# MotorDrive_REVA12.net
KiCad netlist of a schematic drawn in EAGLE
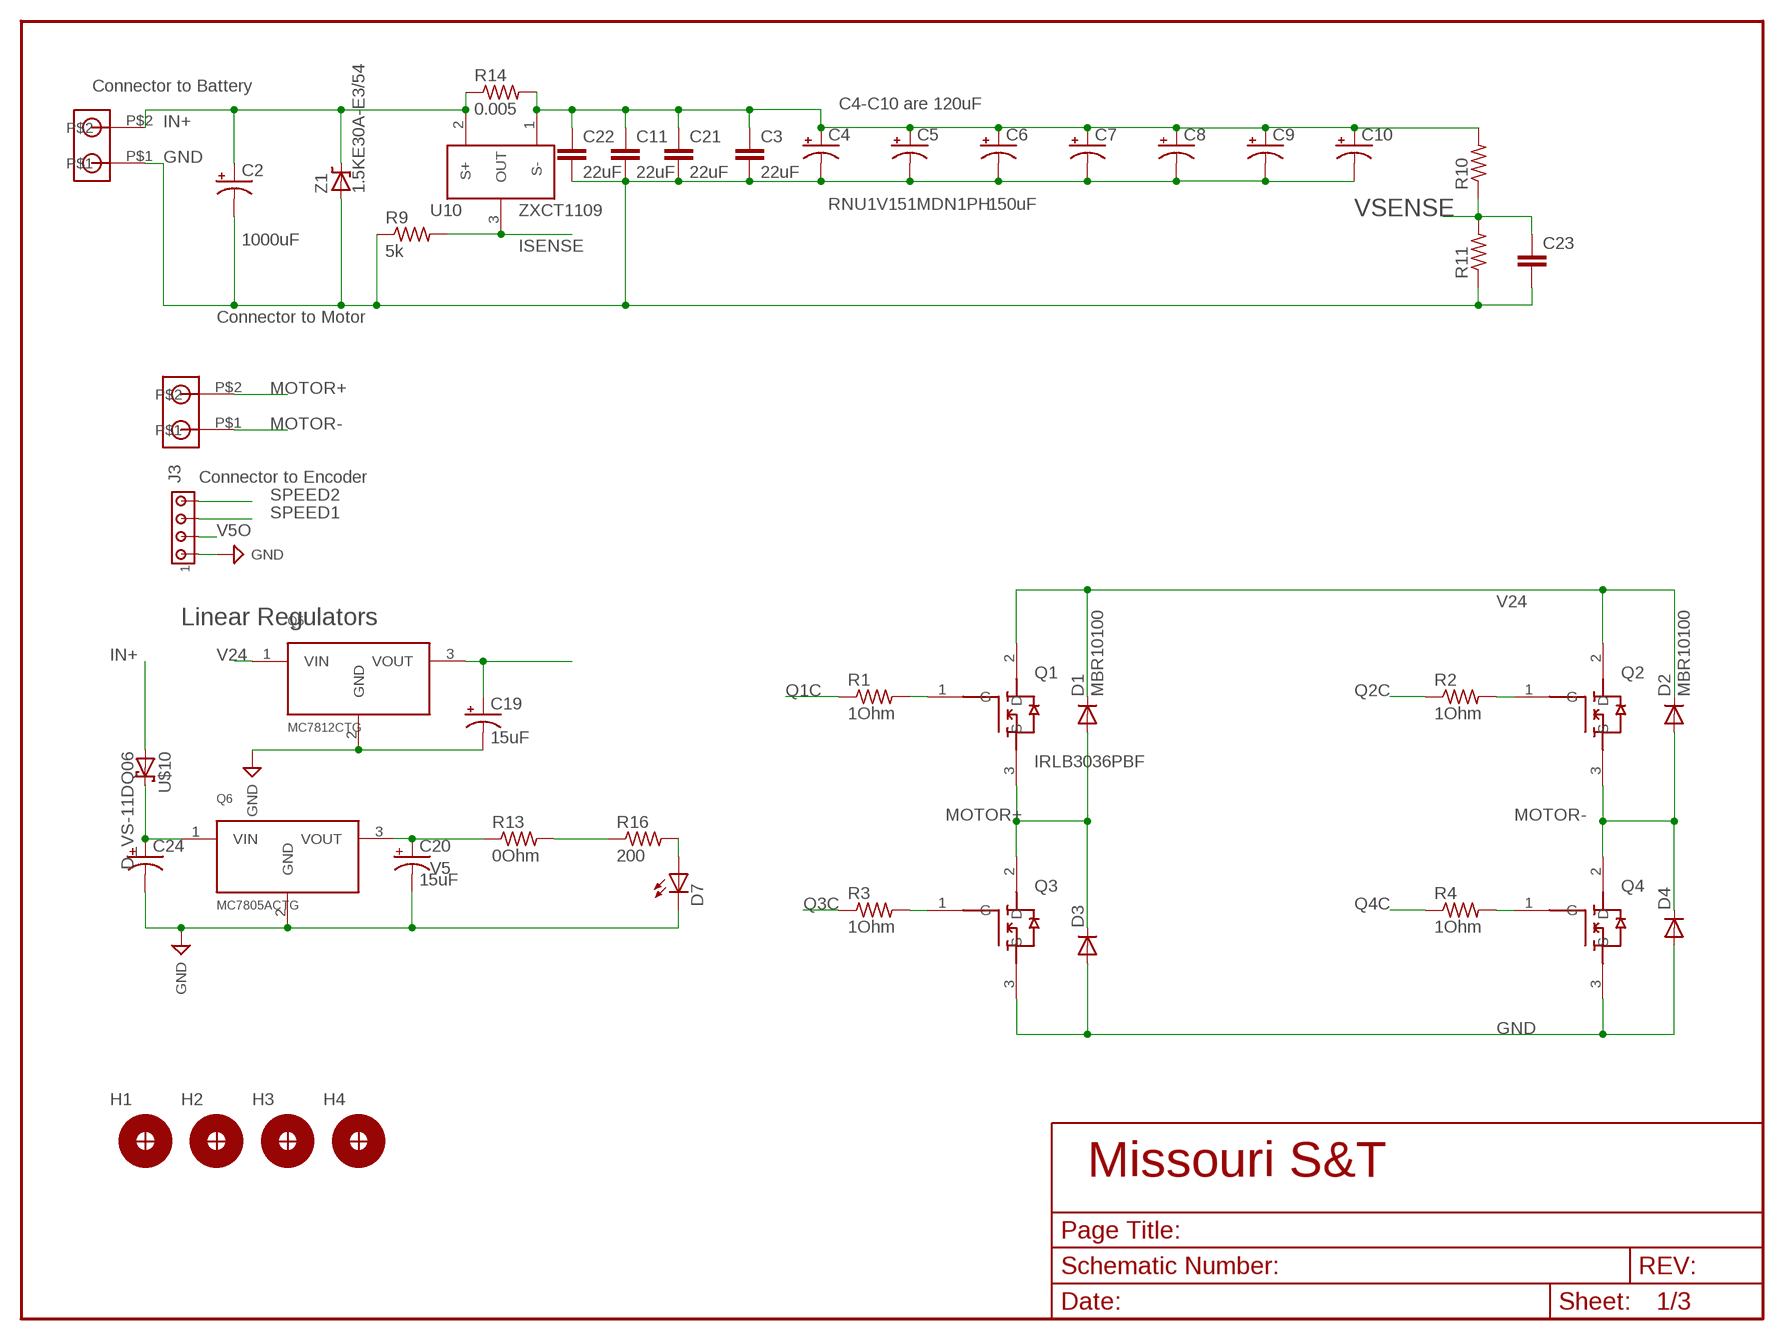
[diagram p0: schematic, sheet 1]
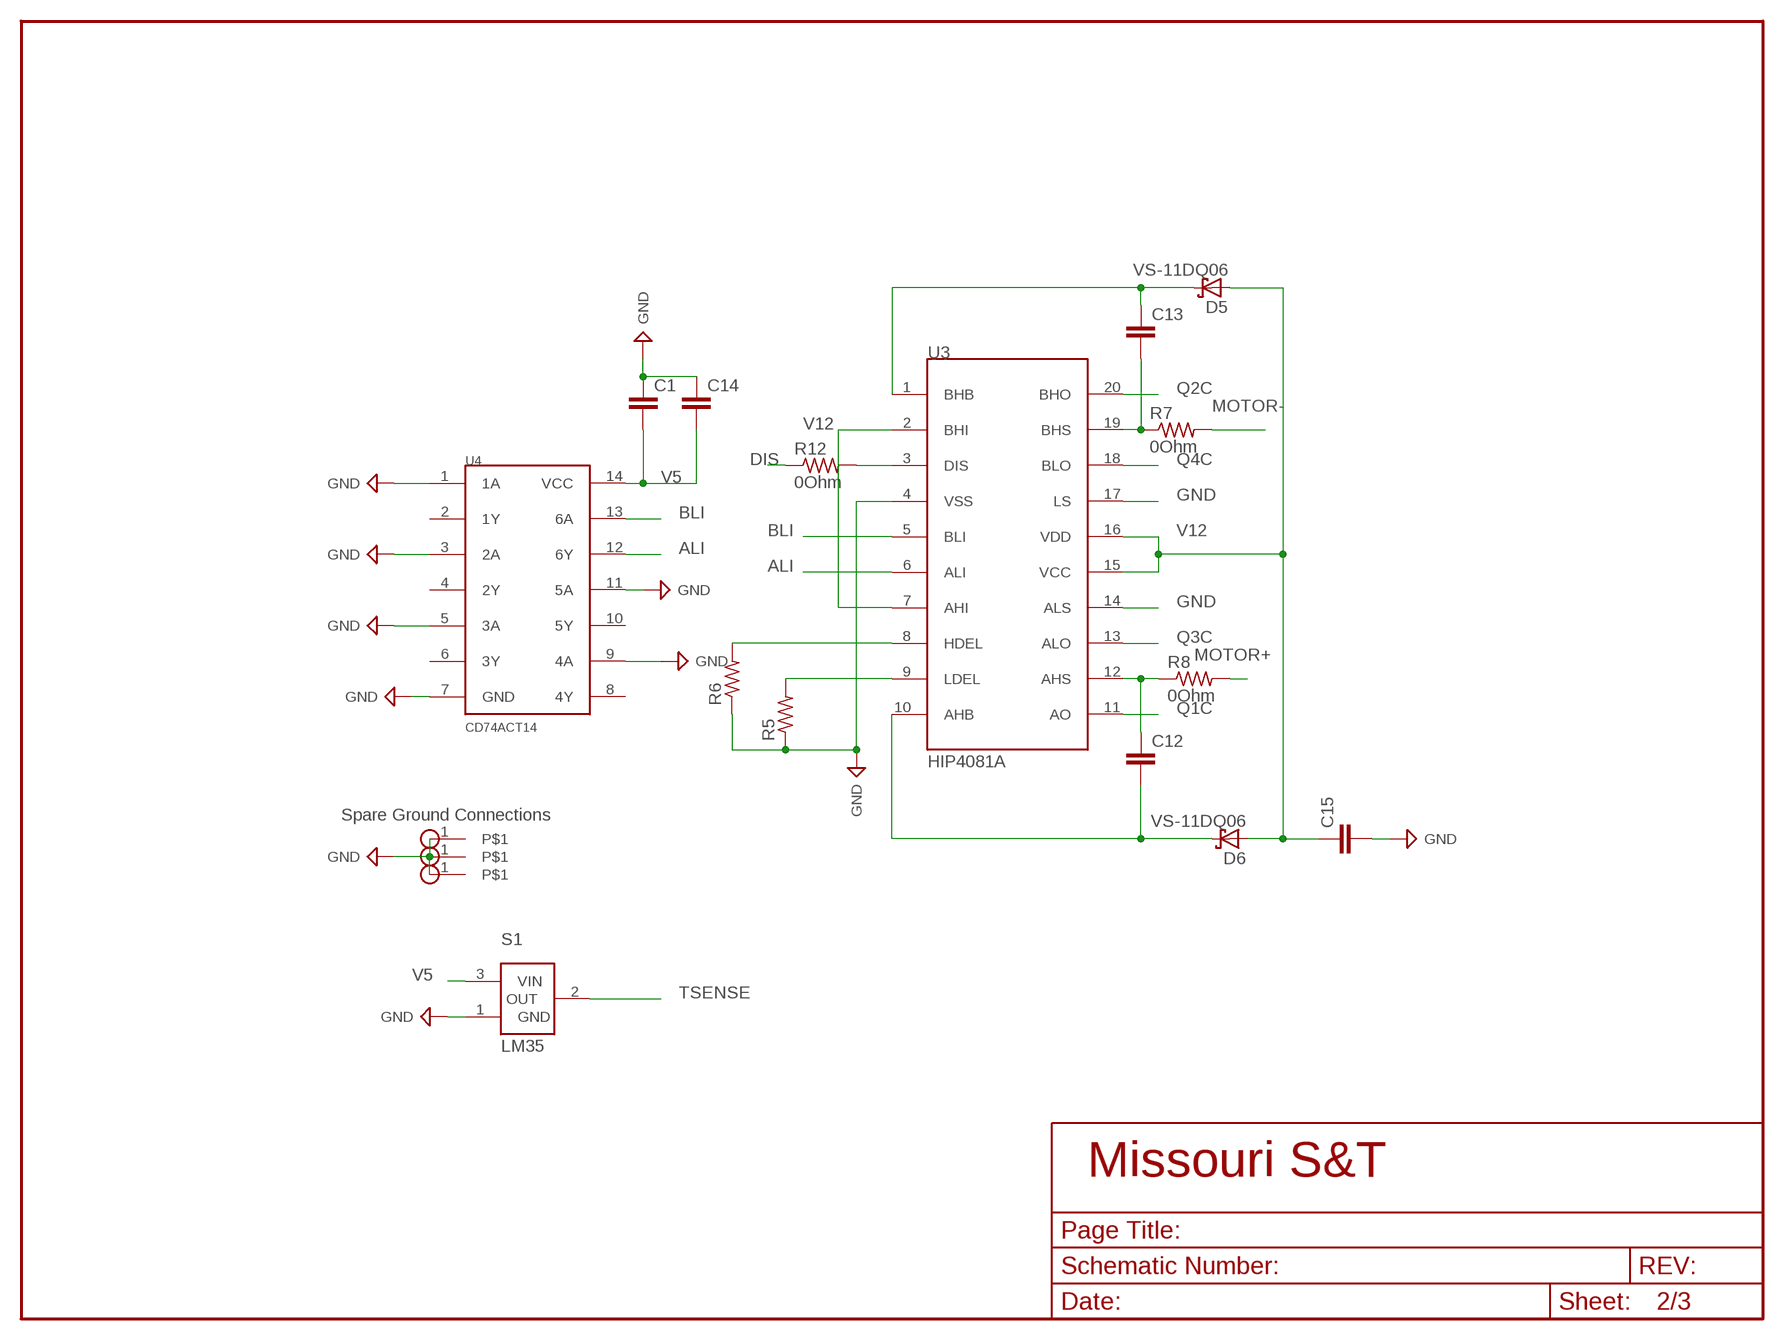
[diagram p1: schematic, sheet 2]
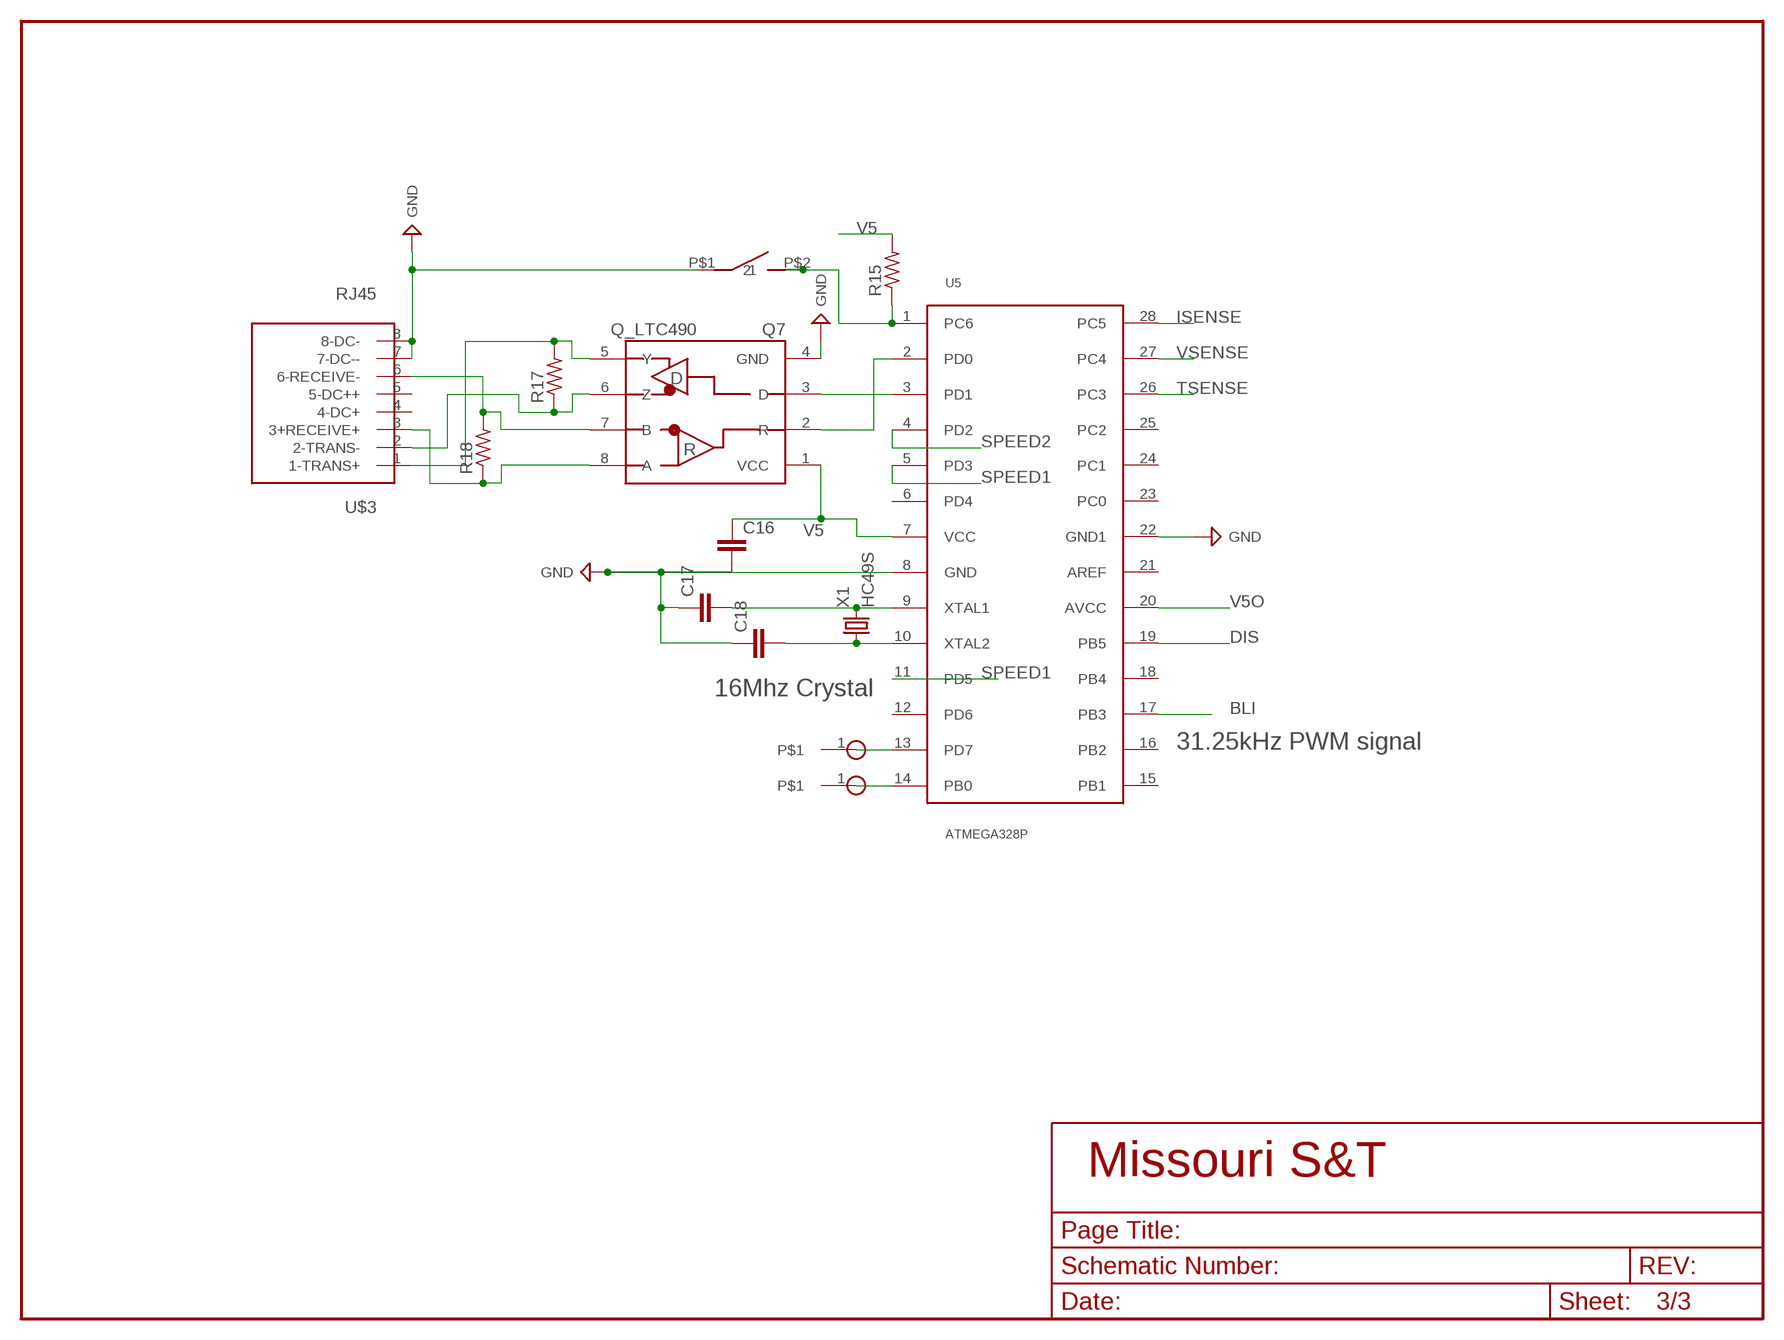
[diagram p2: schematic, sheet 3]

(export (version "E")
  (design (tool "Eeschema 10.0.6"))
  (components
    (comp (ref "C2")
      (value "1000uF")
      (footprint "eagle-import:C_10MM")
      (libsource (lib "eagle-import") (part "C_10MM"))
    )
    (comp (ref "C3")
      (value "22uF")
      (footprint "eagle-import:C_1206")
      (libsource (lib "eagle-import") (part "C_CAP_1206"))
    )
    (comp (ref "C4")
      (value "RNU1V151MDN1PH")
      (footprint "eagle-import:C_10MM")
      (libsource (lib "eagle-import") (part "C_10MM"))
    )
    (comp (ref "C5")
      (value "C_10MM")
      (footprint "eagle-import:C_10MM")
      (libsource (lib "eagle-import") (part "C_10MM"))
    )
    (comp (ref "C6")
      (value "C_10MM")
      (footprint "eagle-import:C_10MM")
      (libsource (lib "eagle-import") (part "C_10MM"))
    )
    (comp (ref "C7")
      (value "C_10MM")
      (footprint "eagle-import:C_10MM")
      (libsource (lib "eagle-import") (part "C_10MM"))
    )
    (comp (ref "C8")
      (value "C_10MM")
      (footprint "eagle-import:C_10MM")
      (libsource (lib "eagle-import") (part "C_10MM"))
    )
    (comp (ref "C9")
      (value "C_10MM")
      (footprint "eagle-import:C_10MM")
      (libsource (lib "eagle-import") (part "C_10MM"))
    )
    (comp (ref "C10")
      (value "150uF")
      (footprint "eagle-import:C_10MM")
      (libsource (lib "eagle-import") (part "C_10MM"))
    )
    (comp (ref "C11")
      (value "22uF")
      (footprint "eagle-import:C_1206")
      (libsource (lib "eagle-import") (part "C_CAP_1206"))
    )
    (comp (ref "C19")
      (value "15uF")
      (footprint "eagle-import:C_2MM")
      (libsource (lib "eagle-import") (part "C_GA1E150"))
    )
    (comp (ref "C20")
      (value "15uF")
      (footprint "eagle-import:C_2MM")
      (libsource (lib "eagle-import") (part "C_GA1E150"))
    )
    (comp (ref "C21")
      (value "22uF")
      (footprint "eagle-import:C_1206")
      (libsource (lib "eagle-import") (part "C_CAP_1206"))
    )
    (comp (ref "C22")
      (value "22uF")
      (footprint "eagle-import:C_1206")
      (libsource (lib "eagle-import") (part "C_CAP_1206"))
    )
    (comp (ref "C23")
      (value "C_CAP_1206")
      (footprint "eagle-import:C_1206")
      (libsource (lib "eagle-import") (part "C_CAP_1206"))
    )
    (comp (ref "C24")
      (value "C_POL_RAD_D8MM_LS200MIL_30MIL")
      (footprint "eagle-import:C_RAD_D8MM_LS200MIL_30MIL")
      (libsource (lib "eagle-import") (part "C_POL_RAD_D8MM_LS200MIL_30MIL"))
    )
    (comp (ref "D1")
      (value "MBR10100")
      (footprint "eagle-import:TO220AC")
      (libsource (lib "eagle-import") (part "D_FFPF10UA60ST"))
    )
    (comp (ref "D2")
      (value "MBR10100")
      (footprint "eagle-import:TO220AC")
      (libsource (lib "eagle-import") (part "D_FFPF10UA60ST"))
    )
    (comp (ref "D3")
      (value "D_FFPF10UA60ST")
      (footprint "eagle-import:TO220AC")
      (libsource (lib "eagle-import") (part "D_FFPF10UA60ST"))
    )
    (comp (ref "D4")
      (value "D_FFPF10UA60ST")
      (footprint "eagle-import:TO220AC")
      (libsource (lib "eagle-import") (part "D_FFPF10UA60ST"))
    )
    (comp (ref "D7")
      (value "D_LED_T1")
      (footprint "eagle-import:D_LED_T1")
      (libsource (lib "eagle-import") (part "D_LED_T1"))
    )
    (comp (ref "H1")
      (value "H_MNTHOLE_#4")
      (footprint "eagle-import:H_MNTHOLE_#4")
      (libsource (lib "eagle-import") (part "H_MNTHOLE_#4"))
    )
    (comp (ref "H2")
      (value "H_MNTHOLE_#4")
      (footprint "eagle-import:H_MNTHOLE_#4")
      (libsource (lib "eagle-import") (part "H_MNTHOLE_#4"))
    )
    (comp (ref "H3")
      (value "H_MNTHOLE_#4")
      (footprint "eagle-import:H_MNTHOLE_#4")
      (libsource (lib "eagle-import") (part "H_MNTHOLE_#4"))
    )
    (comp (ref "H4")
      (value "H_MNTHOLE_#4")
      (footprint "eagle-import:H_MNTHOLE_#4")
      (libsource (lib "eagle-import") (part "H_MNTHOLE_#4"))
    )
    (comp (ref "J1")
      (value "J_1546074-2")
      (footprint "eagle-import:THERM_BLOCK_2")
      (libsource (lib "eagle-import") (part "J_1546074-2"))
    )
    (comp (ref "J2")
      (value "J_1546074-2")
      (footprint "eagle-import:THERM_BLOCK_2")
      (libsource (lib "eagle-import") (part "J_1546074-2"))
    )
    (comp (ref "J3")
      (value "J_HDR1X4_MTA_100MIL")
      (footprint "eagle-import:J_MTA1X4_100MIL")
      (libsource (lib "eagle-import") (part "J_HDR1X4_MTA_100MIL"))
    )
    (comp (ref "Q1")
      (value "IRLB3036PBF")
      (footprint "eagle-import:TO220_6025DG")
      (libsource (lib "eagle-import") (part "Q_IRLB3036PBF"))
    )
    (comp (ref "Q2")
      (value "Q_IRLB3036PBF")
      (footprint "eagle-import:TO220_6025DG")
      (libsource (lib "eagle-import") (part "Q_IRLB3036PBF"))
    )
    (comp (ref "Q3")
      (value "Q_IRLB3036PBF")
      (footprint "eagle-import:TO220_6025DG")
      (libsource (lib "eagle-import") (part "Q_IRLB3036PBF"))
    )
    (comp (ref "Q4")
      (value "Q_IRLB3036PBF")
      (footprint "eagle-import:TO220_6025DG")
      (libsource (lib "eagle-import") (part "Q_IRLB3036PBF"))
    )
    (comp (ref "Q5")
      (value "MC7812CTG")
      (footprint "eagle-import:TO-220")
      (libsource (lib "eagle-import") (part "Q_LDO"))
    )
    (comp (ref "Q6")
      (value "MC7805ACTG")
      (footprint "eagle-import:TO-220")
      (libsource (lib "eagle-import") (part "Q_LDO"))
    )
    (comp (ref "R1")
      (value "1Ohm")
      (footprint "eagle-import:R_1_4W")
      (libsource (lib "eagle-import") (part "R_1/4W"))
    )
    (comp (ref "R2")
      (value "1Ohm")
      (footprint "eagle-import:R_1_4W")
      (libsource (lib "eagle-import") (part "R_1/4W"))
    )
    (comp (ref "R3")
      (value "1Ohm")
      (footprint "eagle-import:R_1_4W")
      (libsource (lib "eagle-import") (part "R_1/4W"))
    )
    (comp (ref "R4")
      (value "1Ohm")
      (footprint "eagle-import:R_1_4W")
      (libsource (lib "eagle-import") (part "R_1/4W"))
    )
    (comp (ref "R9")
      (value "5k")
      (footprint "eagle-import:R_1206")
      (libsource (lib "eagle-import") (part "R_RES_1206"))
    )
    (comp (ref "R10")
      (value "R_RES_1206")
      (footprint "eagle-import:R_1206")
      (libsource (lib "eagle-import") (part "R_RES_1206"))
    )
    (comp (ref "R11")
      (value "R_RES_1206")
      (footprint "eagle-import:R_1206")
      (libsource (lib "eagle-import") (part "R_RES_1206"))
    )
    (comp (ref "R13")
      (value "0Ohm")
      (footprint "eagle-import:R_1_4W")
      (libsource (lib "eagle-import") (part "R_1/4W"))
    )
    (comp (ref "R14")
      (value "0.005")
      (footprint "eagle-import:R_2512")
      (libsource (lib "eagle-import") (part "R_2512"))
    )
    (comp (ref "R16")
      (value "200")
      (footprint "eagle-import:R_1206")
      (libsource (lib "eagle-import") (part "R_RES_1206"))
    )
    (comp (ref "U$10")
      (value "D_VS-11DQ06")
      (footprint "eagle-import:DO-204AL")
      (libsource (lib "eagle-import") (part "D_VS-11DQ06"))
    )
    (comp (ref "U10")
      (value "ZXCT1109")
      (footprint "eagle-import:SOT23")
      (libsource (lib "eagle-import") (part "Q_ZXCT1109"))
    )
    (comp (ref "Z1")
      (value "1.5KE30A-E3/54")
      (footprint "eagle-import:DIODE_D3.5MM_LS15.24MM")
      (libsource (lib "eagle-import") (part "D_1.5KE480A_D3.5MM_LS15.24MM"))
    )
    (comp (ref "C16")
      (value "C_CAP_1206")
      (footprint "eagle-import:C_1206")
      (libsource (lib "eagle-import") (part "C_CAP_1206"))
    )
    (comp (ref "C17")
      (value "C_CAP_1206")
      (footprint "eagle-import:C_1206")
      (libsource (lib "eagle-import") (part "C_CAP_1206"))
    )
    (comp (ref "C18")
      (value "C_CAP_1206")
      (footprint "eagle-import:C_1206")
      (libsource (lib "eagle-import") (part "C_CAP_1206"))
    )
    (comp (ref "J5")
      (value "J_HOLE")
      (footprint "eagle-import:J_AWG20")
      (libsource (lib "eagle-import") (part "J_HOLE"))
    )
    (comp (ref "J6")
      (value "J_HOLE")
      (footprint "eagle-import:J_AWG20")
      (libsource (lib "eagle-import") (part "J_HOLE"))
    )
    (comp (ref "J8")
      (value "J_MC32857")
      (footprint "eagle-import:J_TOGGLE")
      (libsource (lib "eagle-import") (part "J_MC32857"))
    )
    (comp (ref "Q7")
      (value "Q_LTC490")
      (footprint "eagle-import:DIP8")
      (libsource (lib "eagle-import") (part "Q_LTC490"))
    )
    (comp (ref "R15")
      (value "R_RES_1206")
      (footprint "eagle-import:R_1206")
      (libsource (lib "eagle-import") (part "R_RES_1206"))
    )
    (comp (ref "R17")
      (value "R_RES_1206")
      (footprint "eagle-import:R_1206")
      (libsource (lib "eagle-import") (part "R_RES_1206"))
    )
    (comp (ref "R18")
      (value "R_RES_1206")
      (footprint "eagle-import:R_1206")
      (libsource (lib "eagle-import") (part "R_RES_1206"))
    )
    (comp (ref "U$3")
      (value "RJ45")
      (footprint "eagle-import:RJ45-CAT5E")
      (libsource (lib "eagle-import") (part "RJ45"))
    )
    (comp (ref "U5")
      (value "ATMEGA328P")
      (footprint "eagle-import:DIP28")
      (libsource (lib "eagle-import") (part "Q_ATMEGA328P"))
    )
    (comp (ref "X1")
      (value "HC49S")
      (footprint "eagle-import:HC-49")
      (libsource (lib "eagle-import") (part "X_HC49SCRYSTAL"))
    )
    (comp (ref "C1")
      (value "C_CAP_1206")
      (footprint "eagle-import:C_1206")
      (libsource (lib "eagle-import") (part "C_CAP_1206"))
    )
    (comp (ref "C12")
      (value "C_CAP_1206")
      (footprint "eagle-import:C_1206")
      (libsource (lib "eagle-import") (part "C_CAP_1206"))
    )
    (comp (ref "C13")
      (value "C_CAP_1206")
      (footprint "eagle-import:C_1206")
      (libsource (lib "eagle-import") (part "C_CAP_1206"))
    )
    (comp (ref "C14")
      (value "C_CAP_1206")
      (footprint "eagle-import:C_1206")
      (libsource (lib "eagle-import") (part "C_CAP_1206"))
    )
    (comp (ref "C15")
      (value "C_CAP_1206")
      (footprint "eagle-import:C_1206")
      (libsource (lib "eagle-import") (part "C_CAP_1206"))
    )
    (comp (ref "D5")
      (value "VS-11DQ06")
      (footprint "eagle-import:DO-204AL")
      (libsource (lib "eagle-import") (part "D_VS-11DQ06"))
    )
    (comp (ref "D6")
      (value "VS-11DQ06")
      (footprint "eagle-import:DO-204AL")
      (libsource (lib "eagle-import") (part "D_VS-11DQ06"))
    )
    (comp (ref "J10")
      (value "J_HOLE")
      (footprint "eagle-import:J_AWG20")
      (libsource (lib "eagle-import") (part "J_HOLE"))
    )
    (comp (ref "J11")
      (value "J_HOLE")
      (footprint "eagle-import:J_AWG20")
      (libsource (lib "eagle-import") (part "J_HOLE"))
    )
    (comp (ref "J12")
      (value "J_HOLE")
      (footprint "eagle-import:J_AWG20")
      (libsource (lib "eagle-import") (part "J_HOLE"))
    )
    (comp (ref "R5")
      (value "R_RES_1206")
      (footprint "eagle-import:R_1206")
      (libsource (lib "eagle-import") (part "R_RES_1206"))
    )
    (comp (ref "R6")
      (value "R_RES_1206")
      (footprint "eagle-import:R_1206")
      (libsource (lib "eagle-import") (part "R_RES_1206"))
    )
    (comp (ref "R7")
      (value "0Ohm")
      (footprint "eagle-import:R_1_4W")
      (libsource (lib "eagle-import") (part "R_1/4W"))
    )
    (comp (ref "R8")
      (value "0Ohm")
      (footprint "eagle-import:R_1_4W")
      (libsource (lib "eagle-import") (part "R_1/4W"))
    )
    (comp (ref "R12")
      (value "0Ohm")
      (footprint "eagle-import:R_1_4W")
      (libsource (lib "eagle-import") (part "R_1/4W"))
    )
    (comp (ref "S1")
      (value "LM35")
      (footprint "eagle-import:TO-92-3")
      (libsource (lib "eagle-import") (part "Q_LM35"))
    )
    (comp (ref "U3")
      (value "HIP4081A")
      (footprint "eagle-import:DIP20")
      (libsource (lib "eagle-import") (part "Q_HIP4081A"))
    )
    (comp (ref "U4")
      (value "CD74ACT14")
      (footprint "eagle-import:DIP14")
      (libsource (lib "eagle-import") (part "Q_CD74ACT14"))
    )
  )
  (nets
    (net (code "1") (name "ALI") (class "Default")
      (node (ref "U3") (pin "6") (pinfunction "ALI_6") (pintype "bidirectional"))
      (node (ref "U4") (pin "12") (pinfunction "6Y_12") (pintype "bidirectional"))
    )
    (net (code "2") (name "BLI") (class "Default")
      (node (ref "U3") (pin "5") (pinfunction "BLI_5") (pintype "bidirectional"))
      (node (ref "U4") (pin "13") (pinfunction "6A_13") (pintype "bidirectional"))
      (node (ref "U5") (pin "17") (pinfunction "PB3_17") (pintype "bidirectional"))
    )
    (net (code "3") (name "DIS") (class "Default")
      (node (ref "R12") (pin "1") (pinfunction "1_1") (pintype "passive"))
      (node (ref "U5") (pin "19") (pinfunction "PB5_19") (pintype "bidirectional"))
    )
    (net (code "4") (name "GND") (class "Default")
      (node (ref "C1") (pin "1") (pinfunction "1_1") (pintype "passive"))
      (node (ref "C10") (pin "P$2") (pinfunction "-_P$2") (pintype "passive"))
      (node (ref "C11") (pin "2") (pinfunction "2_2") (pintype "passive"))
      (node (ref "C14") (pin "1") (pinfunction "1_1") (pintype "passive"))
      (node (ref "C15") (pin "2") (pinfunction "2_2") (pintype "passive"))
      (node (ref "C16") (pin "2") (pinfunction "2_2") (pintype "passive"))
      (node (ref "C17") (pin "1") (pinfunction "1_1") (pintype "passive"))
      (node (ref "C18") (pin "1") (pinfunction "1_1") (pintype "passive"))
      (node (ref "C19") (pin "-") (pinfunction "-_-") (pintype "passive"))
      (node (ref "C2") (pin "P$2") (pinfunction "-_P$2") (pintype "passive"))
      (node (ref "C20") (pin "-") (pinfunction "-_-") (pintype "passive"))
      (node (ref "C21") (pin "2") (pinfunction "2_2") (pintype "passive"))
      (node (ref "C22") (pin "2") (pinfunction "2_2") (pintype "passive"))
      (node (ref "C23") (pin "2") (pinfunction "2_2") (pintype "passive"))
      (node (ref "C24") (pin "-") (pinfunction "-_-") (pintype "passive"))
      (node (ref "C3") (pin "2") (pinfunction "2_2") (pintype "passive"))
      (node (ref "C4") (pin "P$2") (pinfunction "-_P$2") (pintype "passive"))
      (node (ref "C5") (pin "P$2") (pinfunction "-_P$2") (pintype "passive"))
      (node (ref "C6") (pin "P$2") (pinfunction "-_P$2") (pintype "passive"))
      (node (ref "C7") (pin "P$2") (pinfunction "-_P$2") (pintype "passive"))
      (node (ref "C8") (pin "P$2") (pinfunction "-_P$2") (pintype "passive"))
      (node (ref "C9") (pin "P$2") (pinfunction "-_P$2") (pintype "passive"))
      (node (ref "D3") (pin "3") (pinfunction "A_3") (pintype "passive"))
      (node (ref "D4") (pin "3") (pinfunction "A_3") (pintype "passive"))
      (node (ref "D7") (pin "K") (pinfunction "C_K") (pintype "passive"))
      (node (ref "J10") (pin "1") (pinfunction "P$1_1") (pintype "bidirectional"))
      (node (ref "J11") (pin "1") (pinfunction "P$1_1") (pintype "bidirectional"))
      (node (ref "J12") (pin "1") (pinfunction "P$1_1") (pintype "bidirectional"))
      (node (ref "J2") (pin "P$1") (pinfunction "P$1_P$1") (pintype "bidirectional"))
      (node (ref "J3") (pin "1") (pinfunction "1_1") (pintype "passive"))
      (node (ref "J8") (pin "P$1") (pinfunction "1_P$1") (pintype "bidirectional"))
      (node (ref "Q3") (pin "3") (pinfunction "S_3") (pintype "bidirectional"))
      (node (ref "Q4") (pin "3") (pinfunction "S_3") (pintype "bidirectional"))
      (node (ref "Q5") (pin "2") (pinfunction "GND_2") (pintype "bidirectional"))
      (node (ref "Q6") (pin "2") (pinfunction "GND_2") (pintype "bidirectional"))
      (node (ref "Q7") (pin "4") (pinfunction "GND_4") (pintype "bidirectional"))
      (node (ref "R11") (pin "1") (pinfunction "1_1") (pintype "passive"))
      (node (ref "R5") (pin "1") (pinfunction "1_1") (pintype "passive"))
      (node (ref "R6") (pin "1") (pinfunction "1_1") (pintype "passive"))
      (node (ref "R9") (pin "1") (pinfunction "1_1") (pintype "passive"))
      (node (ref "S1") (pin "1") (pinfunction "GND_1") (pintype "bidirectional"))
      (node (ref "U$3") (pin "7") (pinfunction "7-DC--_7") (pintype "bidirectional"))
      (node (ref "U$3") (pin "8") (pinfunction "8-DC-_8") (pintype "bidirectional"))
      (node (ref "U3") (pin "14") (pinfunction "ALS_14") (pintype "bidirectional"))
      (node (ref "U3") (pin "17") (pinfunction "LS_17") (pintype "bidirectional"))
      (node (ref "U3") (pin "4") (pinfunction "VSS_4") (pintype "bidirectional"))
      (node (ref "U4") (pin "1") (pinfunction "1A_1") (pintype "bidirectional"))
      (node (ref "U4") (pin "11") (pinfunction "5A_11") (pintype "bidirectional"))
      (node (ref "U4") (pin "3") (pinfunction "2A_3") (pintype "bidirectional"))
      (node (ref "U4") (pin "5") (pinfunction "3A_5") (pintype "bidirectional"))
      (node (ref "U4") (pin "7") (pinfunction "GND_7") (pintype "bidirectional"))
      (node (ref "U4") (pin "9") (pinfunction "4A_9") (pintype "bidirectional"))
      (node (ref "U5") (pin "22") (pinfunction "GND1_22") (pintype "bidirectional"))
      (node (ref "U5") (pin "8") (pinfunction "GND_8") (pintype "bidirectional"))
      (node (ref "Z1") (pin "A") (pinfunction "A_A") (pintype "passive"))
    )
    (net (code "5") (name "IN+") (class "Default")
      (node (ref "C2") (pin "P$1") (pinfunction "+_P$1") (pintype "passive"))
      (node (ref "J2") (pin "P$2") (pinfunction "P$2_P$2") (pintype "bidirectional"))
      (node (ref "R14") (pin "P$1") (pinfunction "1_P$1") (pintype "passive"))
      (node (ref "U$10") (pin "A") (pinfunction "A_A") (pintype "passive"))
      (node (ref "U10") (pin "2") (pinfunction "S+_2") (pintype "bidirectional"))
      (node (ref "Z1") (pin "C") (pinfunction "K_C") (pintype "passive"))
    )
    (net (code "6") (name "ISENSE") (class "Default")
      (node (ref "R9") (pin "2") (pinfunction "2_2") (pintype "passive"))
      (node (ref "U10") (pin "3") (pinfunction "OUT_3") (pintype "bidirectional"))
      (node (ref "U5") (pin "28") (pinfunction "PC5_28") (pintype "bidirectional"))
    )
    (net (code "7") (name "MOTOR+") (class "Default")
      (node (ref "D1") (pin "3") (pinfunction "A_3") (pintype "passive"))
      (node (ref "D3") (pin "1") (pinfunction "C_1") (pintype "passive"))
      (node (ref "J1") (pin "P$2") (pinfunction "P$2_P$2") (pintype "bidirectional"))
      (node (ref "Q1") (pin "3") (pinfunction "S_3") (pintype "bidirectional"))
      (node (ref "Q3") (pin "2") (pinfunction "D_2") (pintype "bidirectional"))
      (node (ref "R8") (pin "2") (pinfunction "2_2") (pintype "passive"))
    )
    (net (code "8") (name "MOTOR-") (class "Default")
      (node (ref "D2") (pin "3") (pinfunction "A_3") (pintype "passive"))
      (node (ref "D4") (pin "1") (pinfunction "C_1") (pintype "passive"))
      (node (ref "J1") (pin "P$1") (pinfunction "P$1_P$1") (pintype "bidirectional"))
      (node (ref "Q2") (pin "3") (pinfunction "S_3") (pintype "bidirectional"))
      (node (ref "Q4") (pin "2") (pinfunction "D_2") (pintype "bidirectional"))
      (node (ref "R7") (pin "2") (pinfunction "2_2") (pintype "passive"))
    )
    (net (code "9") (name "Net-(D7-PadA)") (class "Default")
      (node (ref "D7") (pin "A") (pinfunction "A_A") (pintype "passive"))
      (node (ref "R16") (pin "2") (pinfunction "2_2") (pintype "passive"))
    )
    (net (code "10") (name "Net-(J5-P$1)") (class "Default")
      (node (ref "J5") (pin "1") (pinfunction "P$1_1") (pintype "bidirectional"))
      (node (ref "U5") (pin "14") (pinfunction "PB0_14") (pintype "bidirectional"))
    )
    (net (code "11") (name "Net-(J6-P$1)") (class "Default")
      (node (ref "J6") (pin "1") (pinfunction "P$1_1") (pintype "bidirectional"))
      (node (ref "U5") (pin "13") (pinfunction "PD7_13") (pintype "bidirectional"))
    )
    (net (code "12") (name "Net-(J8-2)") (class "Default")
      (node (ref "J8") (pin "P$2") (pinfunction "2_P$2") (pintype "bidirectional"))
      (node (ref "R15") (pin "1") (pinfunction "1_1") (pintype "passive"))
      (node (ref "U5") (pin "1") (pinfunction "PC6_1") (pintype "bidirectional"))
    )
    (net (code "13") (name "Net-(Q1-G)") (class "Default")
      (node (ref "Q1") (pin "1") (pinfunction "G_1") (pintype "bidirectional"))
      (node (ref "R1") (pin "2") (pinfunction "2_2") (pintype "passive"))
    )
    (net (code "14") (name "Net-(Q2-G)") (class "Default")
      (node (ref "Q2") (pin "1") (pinfunction "G_1") (pintype "bidirectional"))
      (node (ref "R2") (pin "2") (pinfunction "2_2") (pintype "passive"))
    )
    (net (code "15") (name "Net-(Q3-G)") (class "Default")
      (node (ref "Q3") (pin "1") (pinfunction "G_1") (pintype "bidirectional"))
      (node (ref "R3") (pin "2") (pinfunction "2_2") (pintype "passive"))
    )
    (net (code "16") (name "Net-(Q4-G)") (class "Default")
      (node (ref "Q4") (pin "1") (pinfunction "G_1") (pintype "bidirectional"))
      (node (ref "R4") (pin "2") (pinfunction "2_2") (pintype "passive"))
    )
    (net (code "17") (name "Net-(Q6-VIN)") (class "Default")
      (node (ref "C24") (pin "+") (pinfunction "+_+") (pintype "passive"))
      (node (ref "Q6") (pin "1") (pinfunction "VIN_1") (pintype "bidirectional"))
      (node (ref "U$10") (pin "C") (pinfunction "C_C") (pintype "passive"))
    )
    (net (code "18") (name "Net-(Q7-A)") (class "Default")
      (node (ref "Q7") (pin "8") (pinfunction "A_8") (pintype "bidirectional"))
      (node (ref "R18") (pin "1") (pinfunction "1_1") (pintype "passive"))
      (node (ref "U$3") (pin "3") (pinfunction "3+RECEIVE+_3") (pintype "bidirectional"))
    )
    (net (code "19") (name "Net-(Q7-B)") (class "Default")
      (node (ref "Q7") (pin "7") (pinfunction "B_7") (pintype "bidirectional"))
      (node (ref "R18") (pin "2") (pinfunction "2_2") (pintype "passive"))
      (node (ref "U$3") (pin "6") (pinfunction "6-RECEIVE-_6") (pintype "bidirectional"))
    )
    (net (code "20") (name "Net-(Q7-D)") (class "Default")
      (node (ref "Q7") (pin "3") (pinfunction "D_3") (pintype "bidirectional"))
      (node (ref "U5") (pin "3") (pinfunction "PD1_3") (pintype "bidirectional"))
    )
    (net (code "21") (name "Net-(Q7-R)") (class "Default")
      (node (ref "Q7") (pin "2") (pinfunction "R_2") (pintype "bidirectional"))
      (node (ref "U5") (pin "2") (pinfunction "PD0_2") (pintype "bidirectional"))
    )
    (net (code "22") (name "Net-(Q7-Y)") (class "Default")
      (node (ref "Q7") (pin "5") (pinfunction "Y_5") (pintype "bidirectional"))
      (node (ref "R17") (pin "2") (pinfunction "2_2") (pintype "passive"))
      (node (ref "U$3") (pin "1") (pinfunction "1-TRANS+_1") (pintype "bidirectional"))
    )
    (net (code "23") (name "Net-(Q7-Z)") (class "Default")
      (node (ref "Q7") (pin "6") (pinfunction "Z_6") (pintype "bidirectional"))
      (node (ref "R17") (pin "1") (pinfunction "1_1") (pintype "passive"))
      (node (ref "U$3") (pin "2") (pinfunction "2-TRANS-_2") (pintype "bidirectional"))
    )
    (net (code "24") (name "Net-(U3-AHB)") (class "Default")
      (node (ref "C12") (pin "2") (pinfunction "2_2") (pintype "passive"))
      (node (ref "D6") (pin "C") (pinfunction "C_C") (pintype "passive"))
      (node (ref "U3") (pin "10") (pinfunction "AHB_10") (pintype "bidirectional"))
    )
    (net (code "25") (name "Net-(U3-AHS)") (class "Default")
      (node (ref "C12") (pin "1") (pinfunction "1_1") (pintype "passive"))
      (node (ref "R8") (pin "1") (pinfunction "1_1") (pintype "passive"))
      (node (ref "U3") (pin "12") (pinfunction "AHS_12") (pintype "bidirectional"))
    )
    (net (code "26") (name "Net-(U3-BHB)") (class "Default")
      (node (ref "C13") (pin "1") (pinfunction "1_1") (pintype "passive"))
      (node (ref "D5") (pin "C") (pinfunction "C_C") (pintype "passive"))
      (node (ref "U3") (pin "1") (pinfunction "BHB_1") (pintype "bidirectional"))
    )
    (net (code "27") (name "Net-(U3-BHS)") (class "Default")
      (node (ref "C13") (pin "2") (pinfunction "2_2") (pintype "passive"))
      (node (ref "R7") (pin "1") (pinfunction "1_1") (pintype "passive"))
      (node (ref "U3") (pin "19") (pinfunction "BHS_19") (pintype "bidirectional"))
    )
    (net (code "28") (name "Net-(U3-DIS)") (class "Default")
      (node (ref "R12") (pin "2") (pinfunction "2_2") (pintype "passive"))
      (node (ref "U3") (pin "3") (pinfunction "DIS_3") (pintype "bidirectional"))
    )
    (net (code "29") (name "Net-(U3-HDEL)") (class "Default")
      (node (ref "R6") (pin "2") (pinfunction "2_2") (pintype "passive"))
      (node (ref "U3") (pin "8") (pinfunction "HDEL_8") (pintype "bidirectional"))
    )
    (net (code "30") (name "Net-(U3-LDEL)") (class "Default")
      (node (ref "R5") (pin "2") (pinfunction "2_2") (pintype "passive"))
      (node (ref "U3") (pin "9") (pinfunction "LDEL_9") (pintype "bidirectional"))
    )
    (net (code "31") (name "Net-(U5-XTAL1)") (class "Default")
      (node (ref "C17") (pin "2") (pinfunction "2_2") (pintype "passive"))
      (node (ref "U5") (pin "9") (pinfunction "XTAL1_9") (pintype "bidirectional"))
      (node (ref "X1") (pin "P$2") (pinfunction "2_P$2") (pintype "passive"))
    )
    (net (code "32") (name "Net-(U5-XTAL2)") (class "Default")
      (node (ref "C18") (pin "2") (pinfunction "2_2") (pintype "passive"))
      (node (ref "U5") (pin "10") (pinfunction "XTAL2_10") (pintype "bidirectional"))
      (node (ref "X1") (pin "P$1") (pinfunction "1_P$1") (pintype "passive"))
    )
    (net (code "33") (name "Q1C") (class "Default")
      (node (ref "R1") (pin "1") (pinfunction "1_1") (pintype "passive"))
      (node (ref "U3") (pin "11") (pinfunction "AO_11") (pintype "bidirectional"))
    )
    (net (code "34") (name "Q2C") (class "Default")
      (node (ref "R2") (pin "1") (pinfunction "1_1") (pintype "passive"))
      (node (ref "U3") (pin "20") (pinfunction "BHO_20") (pintype "bidirectional"))
    )
    (net (code "35") (name "Q3C") (class "Default")
      (node (ref "R3") (pin "1") (pinfunction "1_1") (pintype "passive"))
      (node (ref "U3") (pin "13") (pinfunction "ALO_13") (pintype "bidirectional"))
    )
    (net (code "36") (name "Q4C") (class "Default")
      (node (ref "R4") (pin "1") (pinfunction "1_1") (pintype "passive"))
      (node (ref "U3") (pin "18") (pinfunction "BLO_18") (pintype "bidirectional"))
    )
    (net (code "37") (name "SPEED1") (class "Default")
      (node (ref "J3") (pin "3") (pinfunction "3_3") (pintype "passive"))
      (node (ref "U5") (pin "11") (pinfunction "PD5_11") (pintype "bidirectional"))
      (node (ref "U5") (pin "5") (pinfunction "PD3_5") (pintype "bidirectional"))
    )
    (net (code "38") (name "SPEED2") (class "Default")
      (node (ref "J3") (pin "4") (pinfunction "4_4") (pintype "passive"))
      (node (ref "U5") (pin "4") (pinfunction "PD2_4") (pintype "bidirectional"))
    )
    (net (code "39") (name "TSENSE") (class "Default")
      (node (ref "S1") (pin "2") (pinfunction "OUT_2") (pintype "bidirectional"))
      (node (ref "U5") (pin "26") (pinfunction "PC3_26") (pintype "bidirectional"))
    )
    (net (code "40") (name "V5") (class "Default")
      (node (ref "C1") (pin "2") (pinfunction "2_2") (pintype "passive"))
      (node (ref "C14") (pin "2") (pinfunction "2_2") (pintype "passive"))
      (node (ref "C16") (pin "1") (pinfunction "1_1") (pintype "passive"))
      (node (ref "C20") (pin "+") (pinfunction "+_+") (pintype "passive"))
      (node (ref "Q6") (pin "3") (pinfunction "VOUT_3") (pintype "bidirectional"))
      (node (ref "Q7") (pin "1") (pinfunction "VCC_1") (pintype "bidirectional"))
      (node (ref "R13") (pin "1") (pinfunction "1_1") (pintype "passive"))
      (node (ref "R15") (pin "2") (pinfunction "2_2") (pintype "passive"))
      (node (ref "S1") (pin "3") (pinfunction "VIN_3") (pintype "bidirectional"))
      (node (ref "U4") (pin "14") (pinfunction "VCC_14") (pintype "bidirectional"))
      (node (ref "U5") (pin "7") (pinfunction "VCC_7") (pintype "bidirectional"))
    )
    (net (code "41") (name "V5O") (class "Default")
      (node (ref "J3") (pin "2") (pinfunction "2_2") (pintype "passive"))
      (node (ref "R13") (pin "2") (pinfunction "2_2") (pintype "passive"))
      (node (ref "R16") (pin "1") (pinfunction "1_1") (pintype "passive"))
      (node (ref "U5") (pin "20") (pinfunction "AVCC_20") (pintype "bidirectional"))
    )
    (net (code "42") (name "V12") (class "Default")
      (node (ref "C15") (pin "1") (pinfunction "1_1") (pintype "passive"))
      (node (ref "C19") (pin "+") (pinfunction "+_+") (pintype "passive"))
      (node (ref "D5") (pin "A") (pinfunction "A_A") (pintype "passive"))
      (node (ref "D6") (pin "A") (pinfunction "A_A") (pintype "passive"))
      (node (ref "Q5") (pin "3") (pinfunction "VOUT_3") (pintype "bidirectional"))
      (node (ref "U3") (pin "15") (pinfunction "VCC_15") (pintype "bidirectional"))
      (node (ref "U3") (pin "16") (pinfunction "VDD_16") (pintype "bidirectional"))
      (node (ref "U3") (pin "2") (pinfunction "BHI_2") (pintype "bidirectional"))
      (node (ref "U3") (pin "7") (pinfunction "AHI_7") (pintype "bidirectional"))
    )
    (net (code "43") (name "V24") (class "Default")
      (node (ref "C10") (pin "P$1") (pinfunction "+_P$1") (pintype "passive"))
      (node (ref "C11") (pin "1") (pinfunction "1_1") (pintype "passive"))
      (node (ref "C21") (pin "1") (pinfunction "1_1") (pintype "passive"))
      (node (ref "C22") (pin "1") (pinfunction "1_1") (pintype "passive"))
      (node (ref "C3") (pin "1") (pinfunction "1_1") (pintype "passive"))
      (node (ref "C4") (pin "P$1") (pinfunction "+_P$1") (pintype "passive"))
      (node (ref "C5") (pin "P$1") (pinfunction "+_P$1") (pintype "passive"))
      (node (ref "C6") (pin "P$1") (pinfunction "+_P$1") (pintype "passive"))
      (node (ref "C7") (pin "P$1") (pinfunction "+_P$1") (pintype "passive"))
      (node (ref "C8") (pin "P$1") (pinfunction "+_P$1") (pintype "passive"))
      (node (ref "C9") (pin "P$1") (pinfunction "+_P$1") (pintype "passive"))
      (node (ref "D1") (pin "1") (pinfunction "C_1") (pintype "passive"))
      (node (ref "D2") (pin "1") (pinfunction "C_1") (pintype "passive"))
      (node (ref "Q1") (pin "2") (pinfunction "D_2") (pintype "bidirectional"))
      (node (ref "Q2") (pin "2") (pinfunction "D_2") (pintype "bidirectional"))
      (node (ref "Q5") (pin "1") (pinfunction "VIN_1") (pintype "bidirectional"))
      (node (ref "R10") (pin "2") (pinfunction "2_2") (pintype "passive"))
      (node (ref "R14") (pin "P$2") (pinfunction "2_P$2") (pintype "passive"))
      (node (ref "U10") (pin "1") (pinfunction "S-_1") (pintype "bidirectional"))
    )
    (net (code "44") (name "VSENSE") (class "Default")
      (node (ref "C23") (pin "1") (pinfunction "1_1") (pintype "passive"))
      (node (ref "R10") (pin "1") (pinfunction "1_1") (pintype "passive"))
      (node (ref "R11") (pin "2") (pinfunction "2_2") (pintype "passive"))
      (node (ref "U5") (pin "27") (pinfunction "PC4_27") (pintype "bidirectional"))
    )
    (net (code "45") (name "unconnected-(H1-Pad1)") (class "Default")
      (node (ref "H1") (pin "1") (pinfunction "1_1") (pintype "passive"))
    )
    (net (code "46") (name "unconnected-(H2-Pad1)") (class "Default")
      (node (ref "H2") (pin "1") (pinfunction "1_1") (pintype "passive"))
    )
    (net (code "47") (name "unconnected-(H3-Pad1)") (class "Default")
      (node (ref "H3") (pin "1") (pinfunction "1_1") (pintype "passive"))
    )
    (net (code "48") (name "unconnected-(H4-Pad1)") (class "Default")
      (node (ref "H4") (pin "1") (pinfunction "1_1") (pintype "passive"))
    )
    (net (code "49") (name "unconnected-(U$3-4-DC+-Pad4)") (class "Default")
      (node (ref "U$3") (pin "4") (pinfunction "4-DC+_4") (pintype "bidirectional"))
    )
    (net (code "50") (name "unconnected-(U$3-5-DC++-Pad5)") (class "Default")
      (node (ref "U$3") (pin "5") (pinfunction "5-DC++_5") (pintype "bidirectional"))
    )
    (net (code "51") (name "unconnected-(U4-1Y-Pad2)") (class "Default")
      (node (ref "U4") (pin "2") (pinfunction "1Y_2") (pintype "bidirectional"))
    )
    (net (code "52") (name "unconnected-(U4-2Y-Pad4)") (class "Default")
      (node (ref "U4") (pin "4") (pinfunction "2Y_4") (pintype "bidirectional"))
    )
    (net (code "53") (name "unconnected-(U4-3Y-Pad6)") (class "Default")
      (node (ref "U4") (pin "6") (pinfunction "3Y_6") (pintype "bidirectional"))
    )
    (net (code "54") (name "unconnected-(U4-4Y-Pad8)") (class "Default")
      (node (ref "U4") (pin "8") (pinfunction "4Y_8") (pintype "bidirectional"))
    )
    (net (code "55") (name "unconnected-(U4-5Y-Pad10)") (class "Default")
      (node (ref "U4") (pin "10") (pinfunction "5Y_10") (pintype "bidirectional"))
    )
    (net (code "56") (name "unconnected-(U5-AREF-Pad21)") (class "Default")
      (node (ref "U5") (pin "21") (pinfunction "AREF_21") (pintype "bidirectional"))
    )
    (net (code "57") (name "unconnected-(U5-PB1-Pad15)") (class "Default")
      (node (ref "U5") (pin "15") (pinfunction "PB1_15") (pintype "bidirectional"))
    )
    (net (code "58") (name "unconnected-(U5-PB2-Pad16)") (class "Default")
      (node (ref "U5") (pin "16") (pinfunction "PB2_16") (pintype "bidirectional"))
    )
    (net (code "59") (name "unconnected-(U5-PB4-Pad18)") (class "Default")
      (node (ref "U5") (pin "18") (pinfunction "PB4_18") (pintype "bidirectional"))
    )
    (net (code "60") (name "unconnected-(U5-PC0-Pad23)") (class "Default")
      (node (ref "U5") (pin "23") (pinfunction "PC0_23") (pintype "bidirectional"))
    )
    (net (code "61") (name "unconnected-(U5-PC1-Pad24)") (class "Default")
      (node (ref "U5") (pin "24") (pinfunction "PC1_24") (pintype "bidirectional"))
    )
    (net (code "62") (name "unconnected-(U5-PC2-Pad25)") (class "Default")
      (node (ref "U5") (pin "25") (pinfunction "PC2_25") (pintype "bidirectional"))
    )
    (net (code "63") (name "unconnected-(U5-PD4-Pad6)") (class "Default")
      (node (ref "U5") (pin "6") (pinfunction "PD4_6") (pintype "bidirectional"))
    )
    (net (code "64") (name "unconnected-(U5-PD6-Pad12)") (class "Default")
      (node (ref "U5") (pin "12") (pinfunction "PD6_12") (pintype "bidirectional"))
    )
  )
)
